# magloop_ad8129.net
KiCad netlist of a schematic drawn in EAGLE
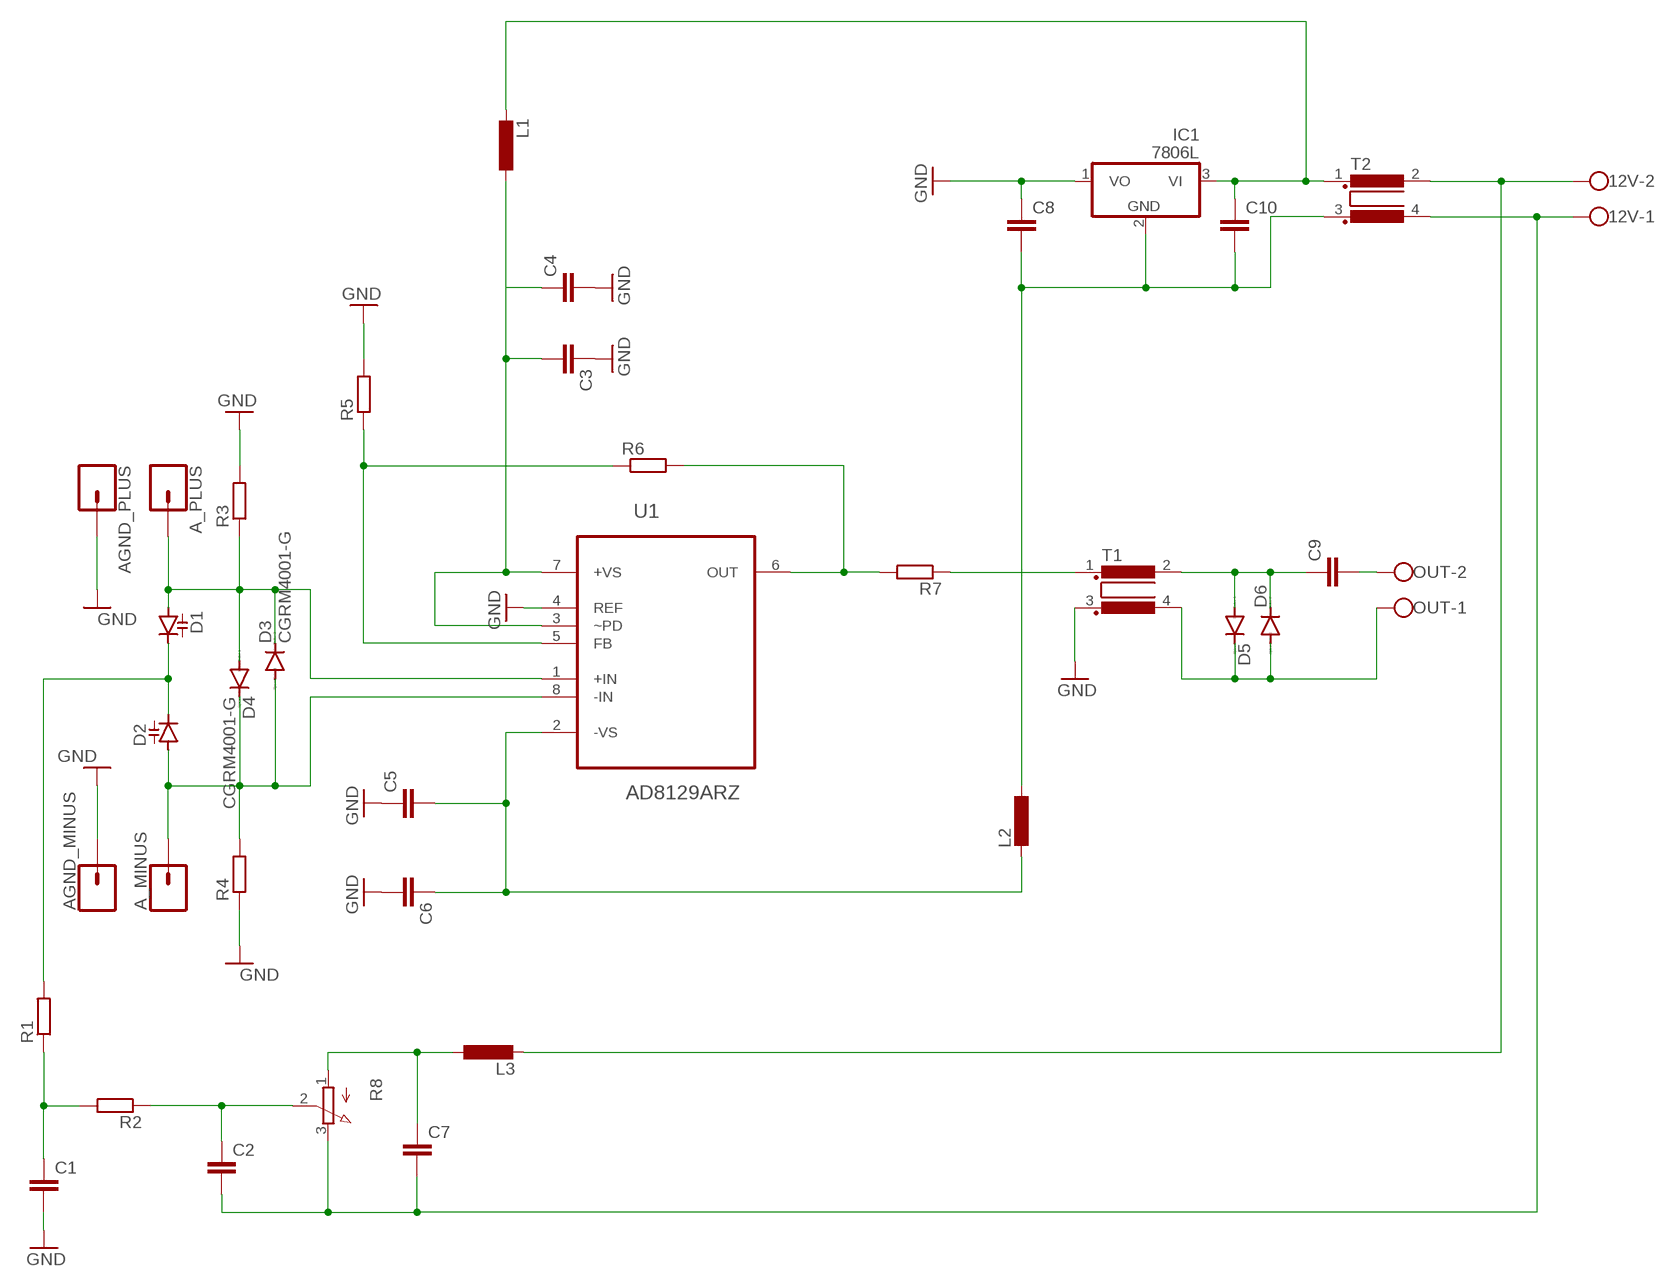
[diagram p0: schematic, sheet 1]

(export (version "E")
  (design (tool "Eeschema 10.0.6"))
  (components
    (comp (ref "12V")
      (value "W237-102")
      (footprint "eagle-import:W237-102")
      (fields (field (name "MPN") "237-102"))
      (libsource (lib "eagle-import") (part "W237-102"))
    )
    (comp (ref "AGND_MINUS")
      (value "CONN_01PTH_2MM")
      (footprint "eagle-import:1X01_2MM")
      (libsource (lib "eagle-import") (part "CONN_01PTH_2MM"))
    )
    (comp (ref "AGND_PLUS")
      (value "CONN_01PTH_2MM")
      (footprint "eagle-import:1X01_2MM")
      (libsource (lib "eagle-import") (part "CONN_01PTH_2MM"))
    )
    (comp (ref "A_MINUS")
      (value "CONN_01PTH_2MM")
      (footprint "eagle-import:1X01_2MM")
      (libsource (lib "eagle-import") (part "CONN_01PTH_2MM"))
    )
    (comp (ref "A_PLUS")
      (value "CONN_01PTH_2MM")
      (footprint "eagle-import:1X01_2MM")
      (libsource (lib "eagle-import") (part "CONN_01PTH_2MM"))
    )
    (comp (ref "C1")
      (value "C-EUC0805K")
      (footprint "eagle-import:C0805K")
      (libsource (lib "eagle-import") (part "C-EUC0805K"))
    )
    (comp (ref "C2")
      (value "C-EUC0805K")
      (footprint "eagle-import:C0805K")
      (libsource (lib "eagle-import") (part "C-EUC0805K"))
    )
    (comp (ref "C3")
      (value "C-EUC1206K")
      (footprint "eagle-import:C1206K")
      (libsource (lib "eagle-import") (part "C-EUC1206K"))
    )
    (comp (ref "C4")
      (value "C-EUC1206K")
      (footprint "eagle-import:C1206K")
      (libsource (lib "eagle-import") (part "C-EUC1206K"))
    )
    (comp (ref "C5")
      (value "C-EUC1206K")
      (footprint "eagle-import:C1206K")
      (libsource (lib "eagle-import") (part "C-EUC1206K"))
    )
    (comp (ref "C6")
      (value "C-EUC1206K")
      (footprint "eagle-import:C1206K")
      (libsource (lib "eagle-import") (part "C-EUC1206K"))
    )
    (comp (ref "C7")
      (value "C-EUC0805K")
      (footprint "eagle-import:C0805K")
      (libsource (lib "eagle-import") (part "C-EUC0805K"))
    )
    (comp (ref "C8")
      (value "C-EUC1206K")
      (footprint "eagle-import:C1206K")
      (libsource (lib "eagle-import") (part "C-EUC1206K"))
    )
    (comp (ref "C9")
      (value "C-EUC1206")
      (footprint "eagle-import:C1206")
      (libsource (lib "eagle-import") (part "C-EUC1206"))
    )
    (comp (ref "C10")
      (value "C-EUC1206K")
      (footprint "eagle-import:C1206K")
      (libsource (lib "eagle-import") (part "C-EUC1206K"))
    )
    (comp (ref "D1")
      (value "DIODE_CAPACITANCE-SOT54H")
      (footprint "eagle-import:SOT54H")
      (libsource (lib "eagle-import") (part "DIODE_CAPACITANCE-SOT54H"))
    )
    (comp (ref "D2")
      (value "DIODE_CAPACITANCE-SOT54H")
      (footprint "eagle-import:SOT54H")
      (libsource (lib "eagle-import") (part "DIODE_CAPACITANCE-SOT54H"))
    )
    (comp (ref "D3")
      (value "CGRM4001-G")
      (footprint "eagle-import:SOD-123_MINI-SMA")
      (libsource (lib "eagle-import") (part "CGRM400-G1"))
    )
    (comp (ref "D4")
      (value "CGRM4001-G")
      (footprint "eagle-import:SOD-123_MINI-SMA")
      (libsource (lib "eagle-import") (part "CGRM400-G1"))
    )
    (comp (ref "D5")
      (value "CGRM4001-G")
      (footprint "eagle-import:SOD-123_MINI-SMA")
      (libsource (lib "eagle-import") (part "CGRM400-G1"))
    )
    (comp (ref "D6")
      (value "CGRM4001-G")
      (footprint "eagle-import:SOD-123_MINI-SMA")
      (libsource (lib "eagle-import") (part "CGRM400-G1"))
    )
    (comp (ref "IC1")
      (value "7806L")
      (footprint "eagle-import:TO92")
      (libsource (lib "eagle-import") (part "78L06"))
    )
    (comp (ref "L1")
      (value "L-EU0207/10")
      (footprint "eagle-import:0207_10")
      (libsource (lib "eagle-import") (part "L-EU0207/10"))
    )
    (comp (ref "L2")
      (value "L-EU0207/10")
      (footprint "eagle-import:0207_10")
      (libsource (lib "eagle-import") (part "L-EU0207/10"))
    )
    (comp (ref "L3")
      (value "L-EU0207/10")
      (footprint "eagle-import:0207_10")
      (libsource (lib "eagle-import") (part "L-EU0207/10"))
    )
    (comp (ref "OUT")
      (value "W237-102")
      (footprint "eagle-import:W237-102")
      (fields (field (name "MPN") "237-102"))
      (libsource (lib "eagle-import") (part "W237-102"))
    )
    (comp (ref "R1")
      (value "R-EU_R0805")
      (footprint "eagle-import:R0805")
      (libsource (lib "eagle-import") (part "R-EU_R0805"))
    )
    (comp (ref "R2")
      (value "R-EU_R0805")
      (footprint "eagle-import:R0805")
      (libsource (lib "eagle-import") (part "R-EU_R0805"))
    )
    (comp (ref "R3")
      (value "R-EU_R1206")
      (footprint "eagle-import:R1206")
      (libsource (lib "eagle-import") (part "R-EU_R1206"))
    )
    (comp (ref "R4")
      (value "R-EU_R1206")
      (footprint "eagle-import:R1206")
      (libsource (lib "eagle-import") (part "R-EU_R1206"))
    )
    (comp (ref "R5")
      (value "R-EU_R0805")
      (footprint "eagle-import:R0805")
      (libsource (lib "eagle-import") (part "R-EU_R0805"))
    )
    (comp (ref "R6")
      (value "R-EU_R0805")
      (footprint "eagle-import:R0805")
      (libsource (lib "eagle-import") (part "R-EU_R0805"))
    )
    (comp (ref "R7")
      (value "R-EU_R1206")
      (footprint "eagle-import:R1206")
      (libsource (lib "eagle-import") (part "R-EU_R1206"))
    )
    (comp (ref "R8")
      (value "3RP/1610N")
      (footprint "eagle-import:3RP_1610N")
      (libsource (lib "eagle-import") (part "3RP/1610N"))
    )
    (comp (ref "T1")
      (value "R1405UB1/2")
      (footprint "eagle-import:B1_2")
      (libsource (lib "eagle-import") (part "R1405UB1/2"))
    )
    (comp (ref "T2")
      (value "R1405UB1/2")
      (footprint "eagle-import:B1_2")
      (libsource (lib "eagle-import") (part "R1405UB1/2"))
    )
    (comp (ref "U1")
      (value "AD8129ARZ")
      (footprint "eagle-import:SOIC127P600X175-8N")
      (fields (field (name "MF") "Analog Devices"))
      (libsource (lib "eagle-import") (part "AD8129ARZ"))
    )
  )
  (nets
    (net (code "1") (name "GND") (class "Default")
      (node (ref "AGND_MINUS") (pin "1") (pinfunction "1_1") (pintype "passive"))
      (node (ref "AGND_PLUS") (pin "1") (pinfunction "1_1") (pintype "passive"))
      (node (ref "C1") (pin "2") (pinfunction "2_2") (pintype "passive"))
      (node (ref "C3") (pin "1") (pinfunction "1_1") (pintype "passive"))
      (node (ref "C4") (pin "2") (pinfunction "2_2") (pintype "passive"))
      (node (ref "C5") (pin "1") (pinfunction "1_1") (pintype "passive"))
      (node (ref "C6") (pin "2") (pinfunction "2_2") (pintype "passive"))
      (node (ref "C8") (pin "1") (pinfunction "1_1") (pintype "passive"))
      (node (ref "IC1") (pin "1") (pinfunction "VO_1") (pintype "passive"))
      (node (ref "R3") (pin "2") (pinfunction "2_2") (pintype "passive"))
      (node (ref "R4") (pin "1") (pinfunction "1_1") (pintype "passive"))
      (node (ref "R5") (pin "2") (pinfunction "2_2") (pintype "passive"))
      (node (ref "T1") (pin "3") (pinfunction "3_3") (pintype "passive"))
      (node (ref "U1") (pin "4") (pinfunction "REF_4") (pintype "input"))
    )
    (net (code "2") (name "Net-(12VA-KL)") (class "Default")
      (node (ref "12V") (pin "1") (pinfunction "KL_1") (pintype "passive"))
      (node (ref "C2") (pin "2") (pinfunction "2_2") (pintype "passive"))
      (node (ref "C7") (pin "2") (pinfunction "2_2") (pintype "passive"))
      (node (ref "R8") (pin "3") (pinfunction "E_3") (pintype "passive"))
      (node (ref "T2") (pin "4") (pinfunction "4_4") (pintype "passive"))
    )
    (net (code "3") (name "Net-(12VB-KL)") (class "Default")
      (node (ref "12V") (pin "2") (pinfunction "KL_2") (pintype "passive"))
      (node (ref "L3") (pin "2") (pinfunction "2_2") (pintype "passive"))
      (node (ref "T2") (pin "2") (pinfunction "2_2") (pintype "passive"))
    )
    (net (code "4") (name "Net-(C1-Pad1)") (class "Default")
      (node (ref "C1") (pin "1") (pinfunction "1_1") (pintype "passive"))
      (node (ref "R1") (pin "1") (pinfunction "1_1") (pintype "passive"))
      (node (ref "R2") (pin "2") (pinfunction "2_2") (pintype "passive"))
    )
    (net (code "5") (name "Net-(C9-Pad1)") (class "Default")
      (node (ref "C9") (pin "1") (pinfunction "1_1") (pintype "passive"))
      (node (ref "D5") (pin "A") (pinfunction "A_A") (pintype "passive"))
      (node (ref "D6") (pin "C") (pinfunction "C_C") (pintype "passive"))
      (node (ref "T1") (pin "2") (pinfunction "2_2") (pintype "passive"))
    )
    (net (code "6") (name "Net-(D1-PadC)") (class "Default")
      (node (ref "D1") (pin "C") (pinfunction "C_C") (pintype "passive"))
      (node (ref "D2") (pin "C") (pinfunction "C_C") (pintype "passive"))
      (node (ref "R1") (pin "2") (pinfunction "2_2") (pintype "passive"))
    )
    (net (code "7") (name "Net-(IC1-GND)") (class "Default")
      (node (ref "C10") (pin "2") (pinfunction "2_2") (pintype "passive"))
      (node (ref "C8") (pin "2") (pinfunction "2_2") (pintype "passive"))
      (node (ref "IC1") (pin "2") (pinfunction "GND_2") (pintype "passive"))
      (node (ref "L2") (pin "1") (pinfunction "1_1") (pintype "passive"))
      (node (ref "T2") (pin "3") (pinfunction "3_3") (pintype "passive"))
    )
    (net (code "8") (name "Net-(IC1-VI)") (class "Default")
      (node (ref "C10") (pin "1") (pinfunction "1_1") (pintype "passive"))
      (node (ref "IC1") (pin "3") (pinfunction "VI_3") (pintype "input"))
      (node (ref "L1") (pin "2") (pinfunction "2_2") (pintype "passive"))
      (node (ref "T2") (pin "1") (pinfunction "1_1") (pintype "passive"))
    )
    (net (code "9") (name "Net-(OUTA-KL)") (class "Default")
      (node (ref "D5") (pin "C") (pinfunction "C_C") (pintype "passive"))
      (node (ref "D6") (pin "A") (pinfunction "A_A") (pintype "passive"))
      (node (ref "OUT") (pin "1") (pinfunction "KL_1") (pintype "passive"))
      (node (ref "T1") (pin "4") (pinfunction "4_4") (pintype "passive"))
    )
    (net (code "10") (name "Net-(OUTB-KL)") (class "Default")
      (node (ref "C9") (pin "2") (pinfunction "2_2") (pintype "passive"))
      (node (ref "OUT") (pin "2") (pinfunction "KL_2") (pintype "passive"))
    )
    (net (code "11") (name "Net-(R7-Pad1)") (class "Default")
      (node (ref "R7") (pin "1") (pinfunction "1_1") (pintype "passive"))
      (node (ref "T1") (pin "1") (pinfunction "1_1") (pintype "passive"))
    )
    (net (code "12") (name "Net-(R8-A)") (class "Default")
      (node (ref "C7") (pin "1") (pinfunction "1_1") (pintype "passive"))
      (node (ref "L3") (pin "1") (pinfunction "1_1") (pintype "passive"))
      (node (ref "R8") (pin "1") (pinfunction "A_1") (pintype "passive"))
    )
    (net (code "13") (name "Net-(R8-S)") (class "Default")
      (node (ref "C2") (pin "1") (pinfunction "1_1") (pintype "passive"))
      (node (ref "R2") (pin "1") (pinfunction "1_1") (pintype "passive"))
      (node (ref "R8") (pin "2") (pinfunction "S_2") (pintype "passive"))
    )
    (net (code "14") (name "Net-(U1-+IN)") (class "Default")
      (node (ref "A_PLUS") (pin "1") (pinfunction "1_1") (pintype "passive"))
      (node (ref "D1") (pin "A") (pinfunction "A_A") (pintype "passive"))
      (node (ref "D3") (pin "C") (pinfunction "C_C") (pintype "passive"))
      (node (ref "D4") (pin "A") (pinfunction "A_A") (pintype "passive"))
      (node (ref "R3") (pin "1") (pinfunction "1_1") (pintype "passive"))
      (node (ref "U1") (pin "1") (pinfunction "+IN_1") (pintype "input"))
    )
    (net (code "15") (name "Net-(U1-+VS)") (class "Default")
      (node (ref "C3") (pin "2") (pinfunction "2_2") (pintype "passive"))
      (node (ref "C4") (pin "1") (pinfunction "1_1") (pintype "passive"))
      (node (ref "L1") (pin "1") (pinfunction "1_1") (pintype "passive"))
      (node (ref "U1") (pin "3") (pinfunction "~{PD}_3") (pintype "passive"))
      (node (ref "U1") (pin "7") (pinfunction "+VS_7") (pintype "power_in"))
    )
    (net (code "16") (name "Net-(U1--IN)") (class "Default")
      (node (ref "A_MINUS") (pin "1") (pinfunction "1_1") (pintype "passive"))
      (node (ref "D2") (pin "A") (pinfunction "A_A") (pintype "passive"))
      (node (ref "D3") (pin "A") (pinfunction "A_A") (pintype "passive"))
      (node (ref "D4") (pin "C") (pinfunction "C_C") (pintype "passive"))
      (node (ref "R4") (pin "2") (pinfunction "2_2") (pintype "passive"))
      (node (ref "U1") (pin "8") (pinfunction "-IN_8") (pintype "input"))
    )
    (net (code "17") (name "Net-(U1--VS)") (class "Default")
      (node (ref "C5") (pin "2") (pinfunction "2_2") (pintype "passive"))
      (node (ref "C6") (pin "1") (pinfunction "1_1") (pintype "passive"))
      (node (ref "L2") (pin "2") (pinfunction "2_2") (pintype "passive"))
      (node (ref "U1") (pin "2") (pinfunction "-VS_2") (pintype "power_in"))
    )
    (net (code "18") (name "Net-(U1-FB)") (class "Default")
      (node (ref "R5") (pin "1") (pinfunction "1_1") (pintype "passive"))
      (node (ref "R6") (pin "1") (pinfunction "1_1") (pintype "passive"))
      (node (ref "U1") (pin "5") (pinfunction "FB_5") (pintype "input"))
    )
    (net (code "19") (name "Net-(U1-OUT)") (class "Default")
      (node (ref "R6") (pin "2") (pinfunction "2_2") (pintype "passive"))
      (node (ref "R7") (pin "2") (pinfunction "2_2") (pintype "passive"))
      (node (ref "U1") (pin "6") (pinfunction "OUT_6") (pintype "output"))
    )
  )
)
